# PIEZO_ver2_sheet1.net
KiCad netlist of a schematic drawn in Altium Designer
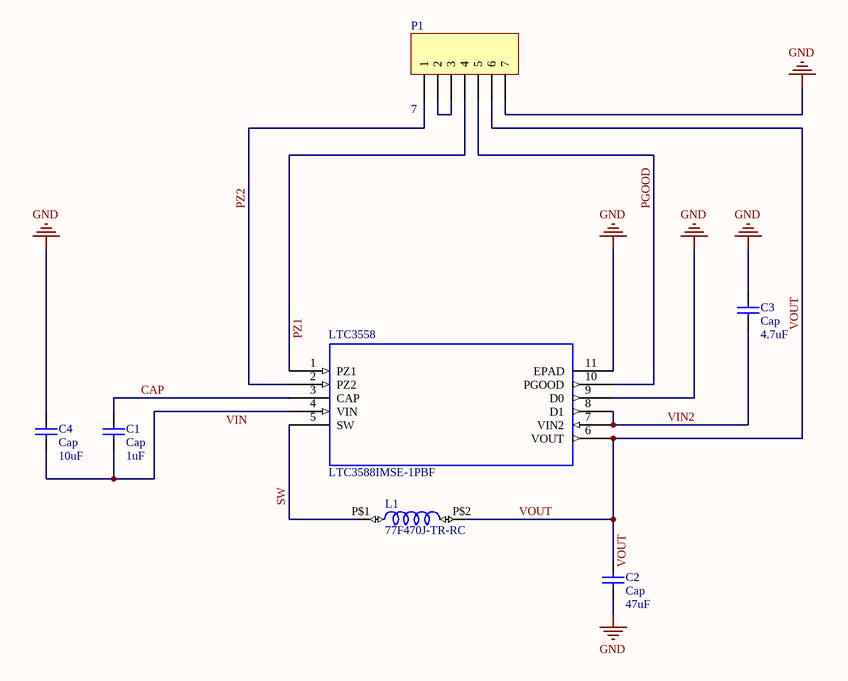
[diagram p0: PIEZO_ver2_sheet1.SchDoc]

(export (version "E")
  (design (tool "Eeschema 10.0.6"))
  (components
    (comp (ref "C1")
      (value "Cap")
      (footprint "Miscellaneous Devices:RAD-0.2")
      (description "Capacitor")
      (fields (field (name "ALTIUM_VALUE") "1uF") (field (name "PUBLISHER") "Altium Limited"))
      (libsource (lib "Miscellaneous Devices") (part "Cap"))
    )
    (comp (ref "C2")
      (value "Cap")
      (footprint "Miscellaneous Devices:RAD-0.2")
      (description "Capacitor")
      (fields (field (name "ALTIUM_VALUE") "47uF") (field (name "PUBLISHER") "Altium Limited"))
      (libsource (lib "Miscellaneous Devices") (part "Cap"))
    )
    (comp (ref "C3")
      (value "Cap")
      (footprint "kondenzator2u2:PCBComponent_1")
      (description "Capacitor")
      (fields (field (name "ALTIUM_VALUE") "4.7uF") (field (name "PUBLISHER") "Altium Limited"))
      (libsource (lib "Miscellaneous Devices") (part "Cap"))
    )
    (comp (ref "C4")
      (value "Cap")
      (footprint "EEUFS0J221B:CAPPRD500W50D500H1100")
      (description "Capacitor")
      (fields (field (name "ALTIUM_VALUE") "10uF") (field (name "PUBLISHER") "Altium Limited"))
      (libsource (lib "Miscellaneous Devices") (part "Cap"))
    )
    (comp (ref "L1")
      (value "77F470J-TR-RC")
      (footprint "77F")
      (description "47 ÂµH Unshielded Drum Core, Wirewound Inductor 340 mA 1.3Ohm Max Axial")
      (fields (field (name "MF") "Bourns"))
      (libsource (lib "77F470J-TR-RC") (part "77F470J-TR-RC"))
    )
    (comp (ref "LTC3558")
      (value "LTC3588IMSE-1PBF")
      (footprint "MSOP-10_MSE")
      (libsource (lib "LTC3588IMSE-1PBF") (part "LTC3588IMSE-1PBF"))
    )
    (comp (ref "P1")
      (value "7")
      (footprint "HDR1X7")
      (description "Header, 7-Pin")
      (fields (field (name "PUBLISHER") "Altium Limited"))
      (libsource (lib "Miscellaneous Connectors") (part "Header 7"))
    )
  )
  (nets
    (net (code "1") (name "/CAP") (class "Default")
      (node (ref "C1") (pin "2") (pinfunction "2_2") (pintype "passive"))
      (node (ref "LTC3558") (pin "3") (pinfunction "CAP_3") (pintype "passive"))
    )
    (net (code "2") (name "/PGOOD") (class "Default")
      (node (ref "LTC3558") (pin "10") (pinfunction "PGOOD_10") (pintype "output"))
      (node (ref "P1") (pin "5") (pinfunction "5_5") (pintype "passive"))
    )
    (net (code "3") (name "/PZ1") (class "Default")
      (node (ref "LTC3558") (pin "1") (pinfunction "PZ1_1") (pintype "input"))
      (node (ref "P1") (pin "4") (pinfunction "4_4") (pintype "passive"))
    )
    (net (code "4") (name "/PZ2") (class "Default")
      (node (ref "LTC3558") (pin "2") (pinfunction "PZ2_2") (pintype "input"))
      (node (ref "P1") (pin "1") (pinfunction "1_1") (pintype "passive"))
    )
    (net (code "5") (name "/SW") (class "Default")
      (node (ref "L1") (pin "P$1") (pinfunction "P$1_P$1") (pintype "bidirectional"))
      (node (ref "LTC3558") (pin "5") (pinfunction "SW_5") (pintype "passive"))
    )
    (net (code "6") (name "/VIN") (class "Default")
      (node (ref "C1") (pin "1") (pinfunction "1_1") (pintype "passive"))
      (node (ref "C4") (pin "1") (pinfunction "1_1") (pintype "passive"))
      (node (ref "LTC3558") (pin "4") (pinfunction "VIN_4") (pintype "input"))
    )
    (net (code "7") (name "/VIN2") (class "Default")
      (node (ref "C3") (pin "1") (pinfunction "1_1") (pintype "passive"))
      (node (ref "LTC3558") (pin "7") (pinfunction "VIN2_7") (pintype "input"))
      (node (ref "LTC3558") (pin "8") (pinfunction "D1_8") (pintype "output"))
    )
    (net (code "8") (name "/VOUT") (class "Default")
      (node (ref "C2") (pin "2") (pinfunction "2_2") (pintype "passive"))
      (node (ref "L1") (pin "P$2") (pinfunction "P$2_P$2") (pintype "bidirectional"))
      (node (ref "LTC3558") (pin "6") (pinfunction "VOUT_6") (pintype "output"))
      (node (ref "P1") (pin "6") (pinfunction "6_6") (pintype "passive"))
    )
    (net (code "9") (name "GND") (class "Default")
      (node (ref "C2") (pin "1") (pinfunction "1_1") (pintype "passive"))
      (node (ref "C3") (pin "2") (pinfunction "2_2") (pintype "passive"))
      (node (ref "C4") (pin "2") (pinfunction "2_2") (pintype "passive"))
      (node (ref "LTC3558") (pin "11") (pinfunction "EPAD_11") (pintype "passive"))
      (node (ref "LTC3558") (pin "9") (pinfunction "D0_9") (pintype "output"))
      (node (ref "P1") (pin "7") (pinfunction "7_7") (pintype "passive"))
    )
    (net (code "10") (name "Net-(P1-Pad2)") (class "Default")
      (node (ref "P1") (pin "2") (pinfunction "2_2") (pintype "passive"))
      (node (ref "P1") (pin "3") (pinfunction "3_3") (pintype "passive"))
    )
  )
)
